# RedBoardTied.net
KiCad netlist of a schematic drawn in EAGLE
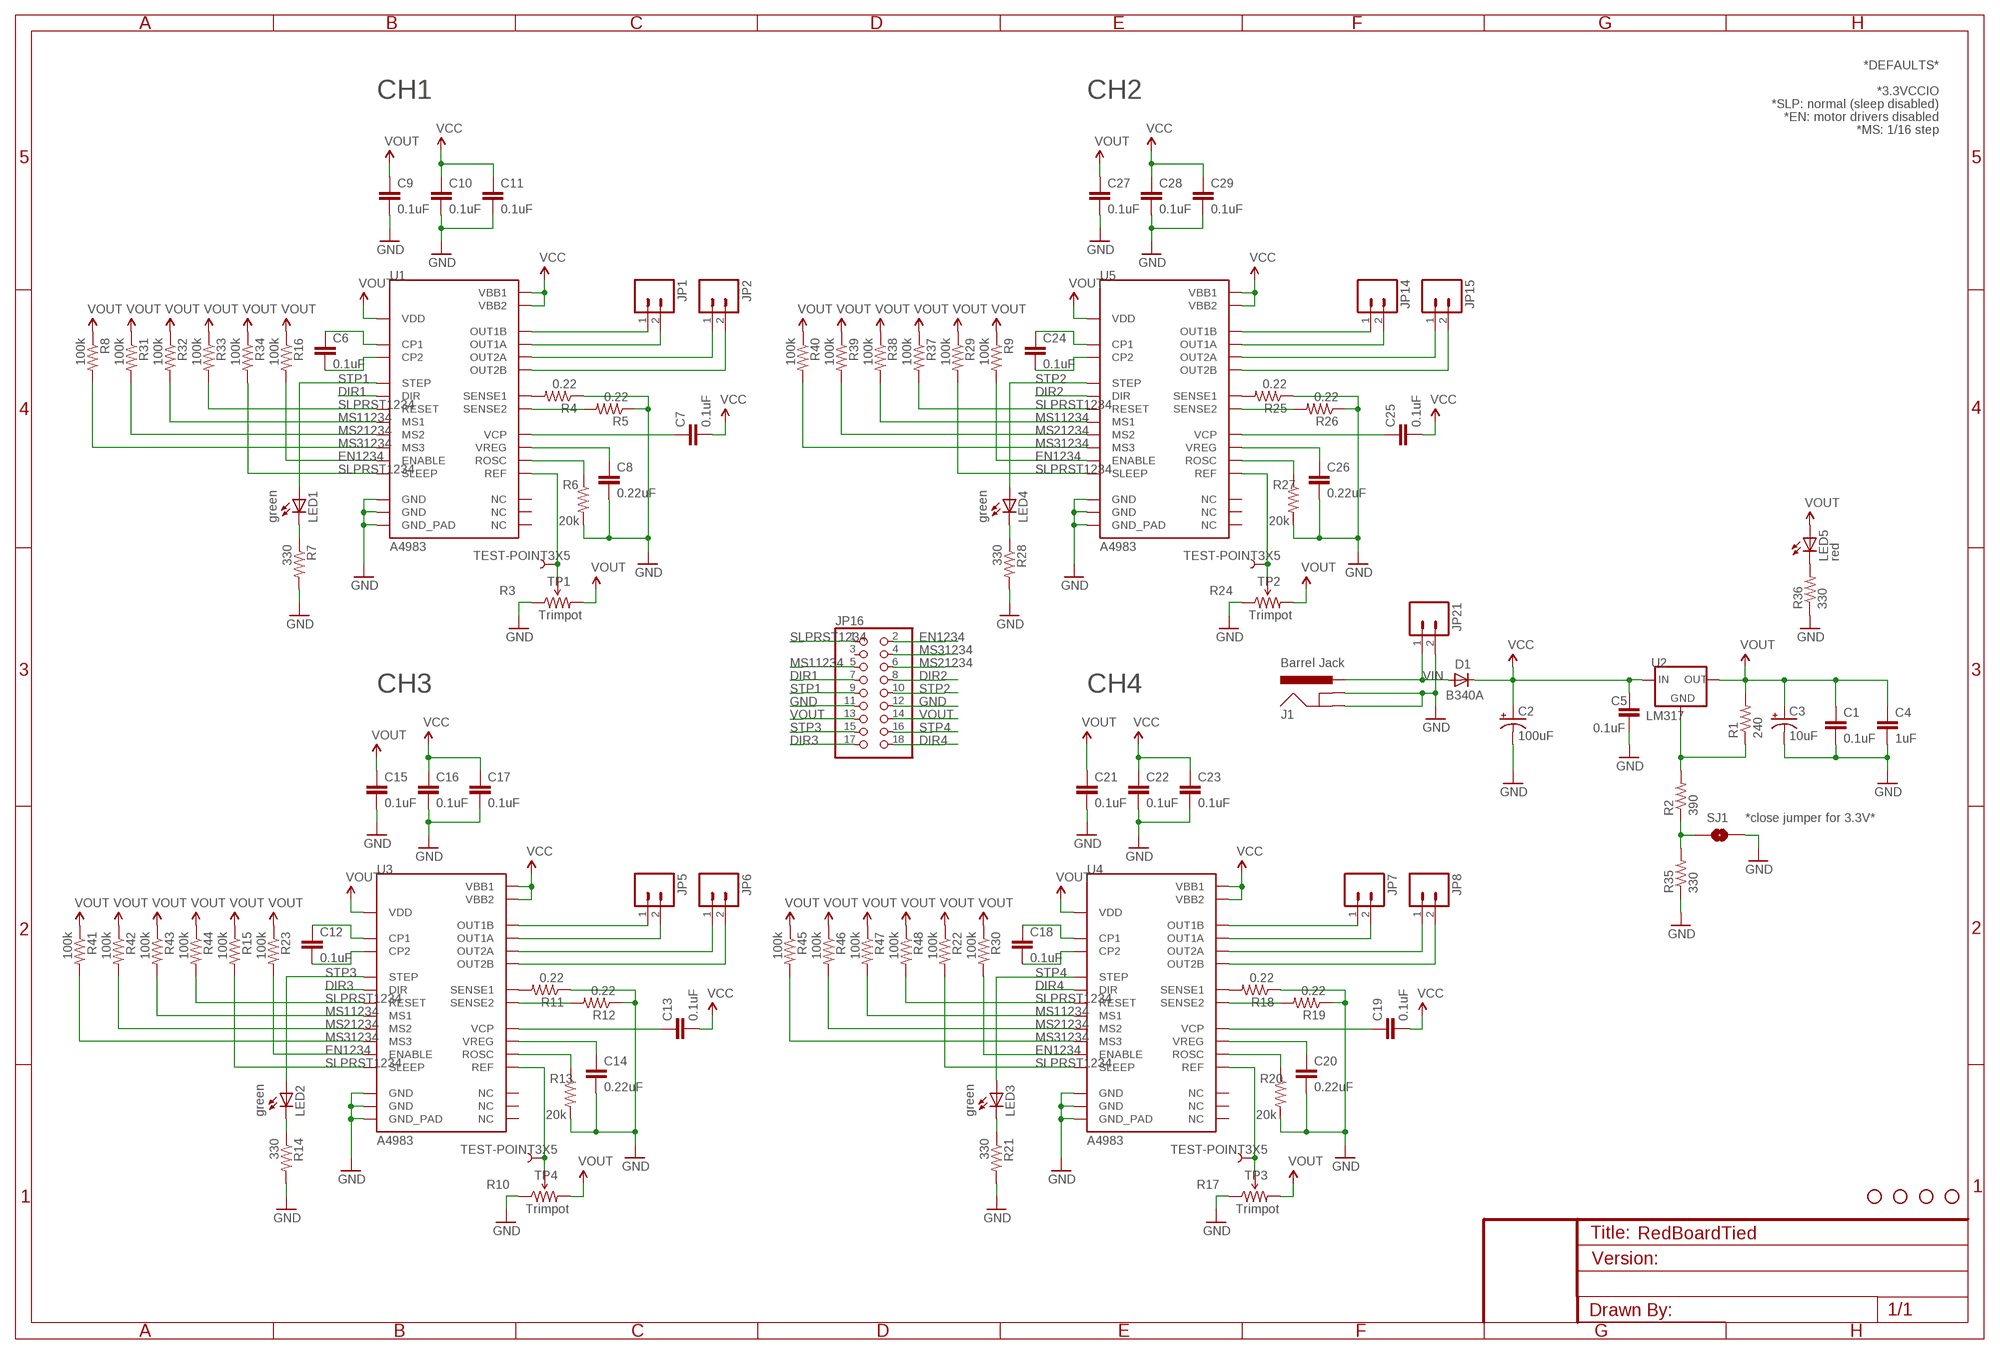
[diagram p0: schematic, sheet 1]

(export (version "E")
  (design (tool "Eeschema 10.0.6"))
  (components
    (comp (ref "C1")
      (value "0.1uF")
      (footprint "eagle-import:0402-CAP")
      (libsource (lib "eagle-import") (part "CAP0402-CAP"))
    )
    (comp (ref "C2")
      (value "100uF")
      (footprint "eagle-import:PANASONIC_G")
      (libsource (lib "eagle-import") (part "CAP_POLG"))
    )
    (comp (ref "C3")
      (value "10uF")
      (footprint "eagle-import:EIA3216")
      (libsource (lib "eagle-import") (part "CAP_POL1206"))
    )
    (comp (ref "C4")
      (value "1uF")
      (footprint "eagle-import:0805")
      (libsource (lib "eagle-import") (part "CAP0805"))
    )
    (comp (ref "C5")
      (value "0.1uF")
      (footprint "eagle-import:0402-CAP")
      (libsource (lib "eagle-import") (part "CAP0402-CAP"))
    )
    (comp (ref "C6")
      (value "0.1uF")
      (footprint "eagle-import:0402-CAP")
      (libsource (lib "eagle-import") (part "CAP0402-CAP"))
    )
    (comp (ref "C7")
      (value "0.1uF")
      (footprint "eagle-import:0402-CAP")
      (libsource (lib "eagle-import") (part "CAP0402-CAP"))
    )
    (comp (ref "C8")
      (value "0.22uF")
      (footprint "eagle-import:0402-CAP")
      (libsource (lib "eagle-import") (part "CAP0402-CAP"))
    )
    (comp (ref "C9")
      (value "0.1uF")
      (footprint "eagle-import:0402-CAP")
      (libsource (lib "eagle-import") (part "CAP0402-CAP"))
    )
    (comp (ref "C10")
      (value "0.1uF")
      (footprint "eagle-import:0402-CAP")
      (libsource (lib "eagle-import") (part "CAP0402-CAP"))
    )
    (comp (ref "C11")
      (value "0.1uF")
      (footprint "eagle-import:0402-CAP")
      (libsource (lib "eagle-import") (part "CAP0402-CAP"))
    )
    (comp (ref "C12")
      (value "0.1uF")
      (footprint "eagle-import:0402-CAP")
      (libsource (lib "eagle-import") (part "CAP0402-CAP"))
    )
    (comp (ref "C13")
      (value "0.1uF")
      (footprint "eagle-import:0402-CAP")
      (libsource (lib "eagle-import") (part "CAP0402-CAP"))
    )
    (comp (ref "C14")
      (value "0.22uF")
      (footprint "eagle-import:0402-CAP")
      (libsource (lib "eagle-import") (part "CAP0402-CAP"))
    )
    (comp (ref "C15")
      (value "0.1uF")
      (footprint "eagle-import:0402-CAP")
      (libsource (lib "eagle-import") (part "CAP0402-CAP"))
    )
    (comp (ref "C16")
      (value "0.1uF")
      (footprint "eagle-import:0402-CAP")
      (libsource (lib "eagle-import") (part "CAP0402-CAP"))
    )
    (comp (ref "C17")
      (value "0.1uF")
      (footprint "eagle-import:0402-CAP")
      (libsource (lib "eagle-import") (part "CAP0402-CAP"))
    )
    (comp (ref "C18")
      (value "0.1uF")
      (footprint "eagle-import:0402-CAP")
      (libsource (lib "eagle-import") (part "CAP0402-CAP"))
    )
    (comp (ref "C19")
      (value "0.1uF")
      (footprint "eagle-import:0402-CAP")
      (libsource (lib "eagle-import") (part "CAP0402-CAP"))
    )
    (comp (ref "C20")
      (value "0.22uF")
      (footprint "eagle-import:0402-CAP")
      (libsource (lib "eagle-import") (part "CAP0402-CAP"))
    )
    (comp (ref "C21")
      (value "0.1uF")
      (footprint "eagle-import:0402-CAP")
      (libsource (lib "eagle-import") (part "CAP0402-CAP"))
    )
    (comp (ref "C22")
      (value "0.1uF")
      (footprint "eagle-import:0402-CAP")
      (libsource (lib "eagle-import") (part "CAP0402-CAP"))
    )
    (comp (ref "C23")
      (value "0.1uF")
      (footprint "eagle-import:0402-CAP")
      (libsource (lib "eagle-import") (part "CAP0402-CAP"))
    )
    (comp (ref "C24")
      (value "0.1uF")
      (footprint "eagle-import:0402-CAP")
      (libsource (lib "eagle-import") (part "CAP0402-CAP"))
    )
    (comp (ref "C25")
      (value "0.1uF")
      (footprint "eagle-import:0402-CAP")
      (libsource (lib "eagle-import") (part "CAP0402-CAP"))
    )
    (comp (ref "C26")
      (value "0.22uF")
      (footprint "eagle-import:0402-CAP")
      (libsource (lib "eagle-import") (part "CAP0402-CAP"))
    )
    (comp (ref "C27")
      (value "0.1uF")
      (footprint "eagle-import:0402-CAP")
      (libsource (lib "eagle-import") (part "CAP0402-CAP"))
    )
    (comp (ref "C28")
      (value "0.1uF")
      (footprint "eagle-import:0402-CAP")
      (libsource (lib "eagle-import") (part "CAP0402-CAP"))
    )
    (comp (ref "C29")
      (value "0.1uF")
      (footprint "eagle-import:0402-CAP")
      (libsource (lib "eagle-import") (part "CAP0402-CAP"))
    )
    (comp (ref "D1")
      (value "B340A")
      (footprint "eagle-import:SMA-DIODE")
      (libsource (lib "eagle-import") (part "DIODESMA"))
    )
    (comp (ref "J1")
      (value "Barrel Jack")
      (footprint "eagle-import:POWER_JACK_SMD")
      (libsource (lib "eagle-import") (part "POWER_JACKSMD"))
    )
    (comp (ref "JP1")
      (value "M023.5MM_LOCK")
      (footprint "eagle-import:SCREWTERMINAL-3.5MM-2_LOCK")
      (libsource (lib "eagle-import") (part "M023.5MM_LOCK"))
    )
    (comp (ref "JP2")
      (value "M023.5MM_LOCK")
      (footprint "eagle-import:SCREWTERMINAL-3.5MM-2_LOCK")
      (libsource (lib "eagle-import") (part "M023.5MM_LOCK"))
    )
    (comp (ref "JP5")
      (value "M023.5MM_LOCK")
      (footprint "eagle-import:SCREWTERMINAL-3.5MM-2_LOCK")
      (libsource (lib "eagle-import") (part "M023.5MM_LOCK"))
    )
    (comp (ref "JP6")
      (value "M023.5MM_LOCK")
      (footprint "eagle-import:SCREWTERMINAL-3.5MM-2_LOCK")
      (libsource (lib "eagle-import") (part "M023.5MM_LOCK"))
    )
    (comp (ref "JP7")
      (value "M023.5MM_LOCK")
      (footprint "eagle-import:SCREWTERMINAL-3.5MM-2_LOCK")
      (libsource (lib "eagle-import") (part "M023.5MM_LOCK"))
    )
    (comp (ref "JP8")
      (value "M023.5MM_LOCK")
      (footprint "eagle-import:SCREWTERMINAL-3.5MM-2_LOCK")
      (libsource (lib "eagle-import") (part "M023.5MM_LOCK"))
    )
    (comp (ref "JP9")
      (value "STAND-OFF")
      (footprint "eagle-import:STAND-OFF")
      (libsource (lib "eagle-import") (part "STAND-OFF"))
    )
    (comp (ref "JP10")
      (value "STAND-OFF")
      (footprint "eagle-import:STAND-OFF")
      (libsource (lib "eagle-import") (part "STAND-OFF"))
    )
    (comp (ref "JP11")
      (value "STAND-OFF")
      (footprint "eagle-import:STAND-OFF")
      (libsource (lib "eagle-import") (part "STAND-OFF"))
    )
    (comp (ref "JP12")
      (value "STAND-OFF")
      (footprint "eagle-import:STAND-OFF")
      (libsource (lib "eagle-import") (part "STAND-OFF"))
    )
    (comp (ref "JP14")
      (value "M023.5MM_LOCK")
      (footprint "eagle-import:SCREWTERMINAL-3.5MM-2_LOCK")
      (libsource (lib "eagle-import") (part "M023.5MM_LOCK"))
    )
    (comp (ref "JP15")
      (value "M023.5MM_LOCK")
      (footprint "eagle-import:SCREWTERMINAL-3.5MM-2_LOCK")
      (libsource (lib "eagle-import") (part "M023.5MM_LOCK"))
    )
    (comp (ref "JP16")
      (value "PINHD-2X9")
      (footprint "eagle-import:2X09")
      (libsource (lib "eagle-import") (part "PINHD-2X9"))
    )
    (comp (ref "JP21")
      (value "M02PTH")
      (footprint "eagle-import:1X02")
      (libsource (lib "eagle-import") (part "M02PTH"))
    )
    (comp (ref "LED1")
      (value "green")
      (footprint "eagle-import:LED-0603")
      (libsource (lib "eagle-import") (part "LED0603"))
    )
    (comp (ref "LED2")
      (value "green")
      (footprint "eagle-import:LED-0603")
      (libsource (lib "eagle-import") (part "LED0603"))
    )
    (comp (ref "LED3")
      (value "green")
      (footprint "eagle-import:LED-0603")
      (libsource (lib "eagle-import") (part "LED0603"))
    )
    (comp (ref "LED4")
      (value "green")
      (footprint "eagle-import:LED-0603")
      (libsource (lib "eagle-import") (part "LED0603"))
    )
    (comp (ref "LED5")
      (value "red")
      (footprint "eagle-import:LED-0603")
      (libsource (lib "eagle-import") (part "LED0603"))
    )
    (comp (ref "R1")
      (value "240")
      (footprint "eagle-import:0402-RES")
      (libsource (lib "eagle-import") (part "RESISTOR0402-RES"))
    )
    (comp (ref "R2")
      (value "390")
      (footprint "eagle-import:0402-RES")
      (libsource (lib "eagle-import") (part "RESISTOR0402-RES"))
    )
    (comp (ref "R3")
      (value "Trimpot")
      (footprint "eagle-import:TRIMPOT-3MM")
      (libsource (lib "eagle-import") (part "TRIMPOTSMD"))
    )
    (comp (ref "R4")
      (value "0.22")
      (footprint "eagle-import:0805")
      (libsource (lib "eagle-import") (part "RESISTOR0805-RES"))
    )
    (comp (ref "R5")
      (value "0.22")
      (footprint "eagle-import:0805")
      (libsource (lib "eagle-import") (part "RESISTOR0805-RES"))
    )
    (comp (ref "R6")
      (value "20k")
      (footprint "eagle-import:0402-RES")
      (libsource (lib "eagle-import") (part "RESISTOR0402-RES"))
    )
    (comp (ref "R7")
      (value "330")
      (footprint "eagle-import:0402-RES")
      (libsource (lib "eagle-import") (part "RESISTOR0402-RES"))
    )
    (comp (ref "R8")
      (value "100k")
      (footprint "eagle-import:0402-RES")
      (libsource (lib "eagle-import") (part "RESISTOR0402-RES"))
    )
    (comp (ref "R9")
      (value "100k")
      (footprint "eagle-import:0402-RES")
      (libsource (lib "eagle-import") (part "RESISTOR0402-RES"))
    )
    (comp (ref "R10")
      (value "Trimpot")
      (footprint "eagle-import:TRIMPOT-3MM")
      (libsource (lib "eagle-import") (part "TRIMPOTSMD"))
    )
    (comp (ref "R11")
      (value "0.22")
      (footprint "eagle-import:0805")
      (libsource (lib "eagle-import") (part "RESISTOR0805-RES"))
    )
    (comp (ref "R12")
      (value "0.22")
      (footprint "eagle-import:0805")
      (libsource (lib "eagle-import") (part "RESISTOR0805-RES"))
    )
    (comp (ref "R13")
      (value "20k")
      (footprint "eagle-import:0402-RES")
      (libsource (lib "eagle-import") (part "RESISTOR0402-RES"))
    )
    (comp (ref "R14")
      (value "330")
      (footprint "eagle-import:0402-RES")
      (libsource (lib "eagle-import") (part "RESISTOR0402-RES"))
    )
    (comp (ref "R15")
      (value "100k")
      (footprint "eagle-import:0402-RES")
      (libsource (lib "eagle-import") (part "RESISTOR0402-RES"))
    )
    (comp (ref "R16")
      (value "100k")
      (footprint "eagle-import:0402-RES")
      (libsource (lib "eagle-import") (part "RESISTOR0402-RES"))
    )
    (comp (ref "R17")
      (value "Trimpot")
      (footprint "eagle-import:TRIMPOT-3MM")
      (libsource (lib "eagle-import") (part "TRIMPOTSMD"))
    )
    (comp (ref "R18")
      (value "0.22")
      (footprint "eagle-import:0805")
      (libsource (lib "eagle-import") (part "RESISTOR0805-RES"))
    )
    (comp (ref "R19")
      (value "0.22")
      (footprint "eagle-import:0805")
      (libsource (lib "eagle-import") (part "RESISTOR0805-RES"))
    )
    (comp (ref "R20")
      (value "20k")
      (footprint "eagle-import:0402-RES")
      (libsource (lib "eagle-import") (part "RESISTOR0402-RES"))
    )
    (comp (ref "R21")
      (value "330")
      (footprint "eagle-import:0402-RES")
      (libsource (lib "eagle-import") (part "RESISTOR0402-RES"))
    )
    (comp (ref "R22")
      (value "100k")
      (footprint "eagle-import:0402-RES")
      (libsource (lib "eagle-import") (part "RESISTOR0402-RES"))
    )
    (comp (ref "R23")
      (value "100k")
      (footprint "eagle-import:0402-RES")
      (libsource (lib "eagle-import") (part "RESISTOR0402-RES"))
    )
    (comp (ref "R24")
      (value "Trimpot")
      (footprint "eagle-import:TRIMPOT-3MM")
      (libsource (lib "eagle-import") (part "TRIMPOTSMD"))
    )
    (comp (ref "R25")
      (value "0.22")
      (footprint "eagle-import:0805")
      (libsource (lib "eagle-import") (part "RESISTOR0805-RES"))
    )
    (comp (ref "R26")
      (value "0.22")
      (footprint "eagle-import:0805")
      (libsource (lib "eagle-import") (part "RESISTOR0805-RES"))
    )
    (comp (ref "R27")
      (value "20k")
      (footprint "eagle-import:0402-RES")
      (libsource (lib "eagle-import") (part "RESISTOR0402-RES"))
    )
    (comp (ref "R28")
      (value "330")
      (footprint "eagle-import:0402-RES")
      (libsource (lib "eagle-import") (part "RESISTOR0402-RES"))
    )
    (comp (ref "R29")
      (value "100k")
      (footprint "eagle-import:0402-RES")
      (libsource (lib "eagle-import") (part "RESISTOR0402-RES"))
    )
    (comp (ref "R30")
      (value "100k")
      (footprint "eagle-import:0402-RES")
      (libsource (lib "eagle-import") (part "RESISTOR0402-RES"))
    )
    (comp (ref "R31")
      (value "100k")
      (footprint "eagle-import:0402-RES")
      (libsource (lib "eagle-import") (part "RESISTOR0402-RES"))
    )
    (comp (ref "R32")
      (value "100k")
      (footprint "eagle-import:0402-RES")
      (libsource (lib "eagle-import") (part "RESISTOR0402-RES"))
    )
    (comp (ref "R33")
      (value "100k")
      (footprint "eagle-import:0402-RES")
      (libsource (lib "eagle-import") (part "RESISTOR0402-RES"))
    )
    (comp (ref "R34")
      (value "100k")
      (footprint "eagle-import:0402-RES")
      (libsource (lib "eagle-import") (part "RESISTOR0402-RES"))
    )
    (comp (ref "R35")
      (value "330")
      (footprint "eagle-import:0402-RES")
      (libsource (lib "eagle-import") (part "RESISTOR0402-RES"))
    )
    (comp (ref "R36")
      (value "330")
      (footprint "eagle-import:0402-RES")
      (libsource (lib "eagle-import") (part "RESISTOR0402-RES"))
    )
    (comp (ref "R37")
      (value "100k")
      (footprint "eagle-import:0402-RES")
      (libsource (lib "eagle-import") (part "RESISTOR0402-RES"))
    )
    (comp (ref "R38")
      (value "100k")
      (footprint "eagle-import:0402-RES")
      (libsource (lib "eagle-import") (part "RESISTOR0402-RES"))
    )
    (comp (ref "R39")
      (value "100k")
      (footprint "eagle-import:0402-RES")
      (libsource (lib "eagle-import") (part "RESISTOR0402-RES"))
    )
    (comp (ref "R40")
      (value "100k")
      (footprint "eagle-import:0402-RES")
      (libsource (lib "eagle-import") (part "RESISTOR0402-RES"))
    )
    (comp (ref "R41")
      (value "100k")
      (footprint "eagle-import:0402-RES")
      (libsource (lib "eagle-import") (part "RESISTOR0402-RES"))
    )
    (comp (ref "R42")
      (value "100k")
      (footprint "eagle-import:0402-RES")
      (libsource (lib "eagle-import") (part "RESISTOR0402-RES"))
    )
    (comp (ref "R43")
      (value "100k")
      (footprint "eagle-import:0402-RES")
      (libsource (lib "eagle-import") (part "RESISTOR0402-RES"))
    )
    (comp (ref "R44")
      (value "100k")
      (footprint "eagle-import:0402-RES")
      (libsource (lib "eagle-import") (part "RESISTOR0402-RES"))
    )
    (comp (ref "R45")
      (value "100k")
      (footprint "eagle-import:0402-RES")
      (libsource (lib "eagle-import") (part "RESISTOR0402-RES"))
    )
    (comp (ref "R46")
      (value "100k")
      (footprint "eagle-import:0402-RES")
      (libsource (lib "eagle-import") (part "RESISTOR0402-RES"))
    )
    (comp (ref "R47")
      (value "100k")
      (footprint "eagle-import:0402-RES")
      (libsource (lib "eagle-import") (part "RESISTOR0402-RES"))
    )
    (comp (ref "R48")
      (value "100k")
      (footprint "eagle-import:0402-RES")
      (libsource (lib "eagle-import") (part "RESISTOR0402-RES"))
    )
    (comp (ref "SJ1")
      (value "SOLDERJUMPERNO")
      (footprint "eagle-import:SJ_2S-NO")
      (libsource (lib "eagle-import") (part "SOLDERJUMPERNO"))
    )
    (comp (ref "TP1")
      (value "TEST-POINT3X5")
      (footprint "eagle-import:PAD.03X.05")
      (libsource (lib "eagle-import") (part "TEST-POINT3X5"))
    )
    (comp (ref "TP2")
      (value "TEST-POINT3X5")
      (footprint "eagle-import:PAD.03X.05")
      (libsource (lib "eagle-import") (part "TEST-POINT3X5"))
    )
    (comp (ref "TP3")
      (value "TEST-POINT3X5")
      (footprint "eagle-import:PAD.03X.05")
      (libsource (lib "eagle-import") (part "TEST-POINT3X5"))
    )
    (comp (ref "TP4")
      (value "TEST-POINT3X5")
      (footprint "eagle-import:PAD.03X.05")
      (libsource (lib "eagle-import") (part "TEST-POINT3X5"))
    )
    (comp (ref "U1")
      (value "A4983")
      (footprint "eagle-import:QFN-28-5MM")
      (libsource (lib "eagle-import") (part "A4983"))
    )
    (comp (ref "U2")
      (value "LM317")
      (footprint "eagle-import:DPAK")
      (libsource (lib "eagle-import") (part "V_REG_MC33269DT"))
    )
    (comp (ref "U3")
      (value "A4983")
      (footprint "eagle-import:QFN-28-5MM")
      (libsource (lib "eagle-import") (part "A4983"))
    )
    (comp (ref "U4")
      (value "A4983")
      (footprint "eagle-import:QFN-28-5MM")
      (libsource (lib "eagle-import") (part "A4983"))
    )
    (comp (ref "U5")
      (value "A4983")
      (footprint "eagle-import:QFN-28-5MM")
      (libsource (lib "eagle-import") (part "A4983"))
    )
  )
  (nets
    (net (code "1") (name "/DIR1") (class "Default")
      (node (ref "JP16") (pin "7") (pinfunction "7_7") (pintype "passive"))
      (node (ref "U1") (pin "P$19") (pinfunction "DIR_P$19") (pintype "input"))
    )
    (net (code "2") (name "/DIR2") (class "Default")
      (node (ref "JP16") (pin "8") (pinfunction "8_8") (pintype "passive"))
      (node (ref "U5") (pin "P$19") (pinfunction "DIR_P$19") (pintype "input"))
    )
    (net (code "3") (name "/DIR3") (class "Default")
      (node (ref "JP16") (pin "17") (pinfunction "17_17") (pintype "passive"))
      (node (ref "U3") (pin "P$19") (pinfunction "DIR_P$19") (pintype "input"))
    )
    (net (code "4") (name "/DIR4") (class "Default")
      (node (ref "JP16") (pin "18") (pinfunction "18_18") (pintype "passive"))
      (node (ref "U4") (pin "P$19") (pinfunction "DIR_P$19") (pintype "input"))
    )
    (net (code "5") (name "/EN1234") (class "Default")
      (node (ref "JP16") (pin "2") (pinfunction "2_2") (pintype "passive"))
      (node (ref "R16") (pin "2") (pinfunction "2_2") (pintype "passive"))
      (node (ref "R23") (pin "2") (pinfunction "2_2") (pintype "passive"))
      (node (ref "R30") (pin "2") (pinfunction "2_2") (pintype "passive"))
      (node (ref "R9") (pin "2") (pinfunction "2_2") (pintype "passive"))
      (node (ref "U1") (pin "P$2") (pinfunction "ENABLE_P$2") (pintype "input"))
      (node (ref "U3") (pin "P$2") (pinfunction "ENABLE_P$2") (pintype "input"))
      (node (ref "U4") (pin "P$2") (pinfunction "ENABLE_P$2") (pintype "input"))
      (node (ref "U5") (pin "P$2") (pinfunction "ENABLE_P$2") (pintype "input"))
    )
    (net (code "6") (name "/MS11234") (class "Default")
      (node (ref "JP16") (pin "5") (pinfunction "5_5") (pintype "passive"))
      (node (ref "R32") (pin "2") (pinfunction "2_2") (pintype "passive"))
      (node (ref "R38") (pin "2") (pinfunction "2_2") (pintype "passive"))
      (node (ref "R43") (pin "2") (pinfunction "2_2") (pintype "passive"))
      (node (ref "R47") (pin "2") (pinfunction "2_2") (pintype "passive"))
      (node (ref "U1") (pin "P$9") (pinfunction "MS1_P$9") (pintype "input"))
      (node (ref "U3") (pin "P$9") (pinfunction "MS1_P$9") (pintype "input"))
      (node (ref "U4") (pin "P$9") (pinfunction "MS1_P$9") (pintype "input"))
      (node (ref "U5") (pin "P$9") (pinfunction "MS1_P$9") (pintype "input"))
    )
    (net (code "7") (name "/MS21234") (class "Default")
      (node (ref "JP16") (pin "6") (pinfunction "6_6") (pintype "passive"))
      (node (ref "R31") (pin "2") (pinfunction "2_2") (pintype "passive"))
      (node (ref "R39") (pin "2") (pinfunction "2_2") (pintype "passive"))
      (node (ref "R42") (pin "2") (pinfunction "2_2") (pintype "passive"))
      (node (ref "R46") (pin "2") (pinfunction "2_2") (pintype "passive"))
      (node (ref "U1") (pin "P$10") (pinfunction "MS2_P$10") (pintype "input"))
      (node (ref "U3") (pin "P$10") (pinfunction "MS2_P$10") (pintype "input"))
      (node (ref "U4") (pin "P$10") (pinfunction "MS2_P$10") (pintype "input"))
      (node (ref "U5") (pin "P$10") (pinfunction "MS2_P$10") (pintype "input"))
    )
    (net (code "8") (name "/MS31234") (class "Default")
      (node (ref "JP16") (pin "4") (pinfunction "4_4") (pintype "passive"))
      (node (ref "R40") (pin "2") (pinfunction "2_2") (pintype "passive"))
      (node (ref "R41") (pin "2") (pinfunction "2_2") (pintype "passive"))
      (node (ref "R45") (pin "2") (pinfunction "2_2") (pintype "passive"))
      (node (ref "R8") (pin "2") (pinfunction "2_2") (pintype "passive"))
      (node (ref "U1") (pin "P$11") (pinfunction "MS3_P$11") (pintype "input"))
      (node (ref "U3") (pin "P$11") (pinfunction "MS3_P$11") (pintype "input"))
      (node (ref "U4") (pin "P$11") (pinfunction "MS3_P$11") (pintype "input"))
      (node (ref "U5") (pin "P$11") (pinfunction "MS3_P$11") (pintype "input"))
    )
    (net (code "9") (name "/SLPRST1234") (class "Default")
      (node (ref "JP16") (pin "1") (pinfunction "1_1") (pintype "passive"))
      (node (ref "R15") (pin "2") (pinfunction "2_2") (pintype "passive"))
      (node (ref "R22") (pin "2") (pinfunction "2_2") (pintype "passive"))
      (node (ref "R29") (pin "2") (pinfunction "2_2") (pintype "passive"))
      (node (ref "R33") (pin "2") (pinfunction "2_2") (pintype "passive"))
      (node (ref "R34") (pin "2") (pinfunction "2_2") (pintype "passive"))
      (node (ref "R37") (pin "2") (pinfunction "2_2") (pintype "passive"))
      (node (ref "R44") (pin "2") (pinfunction "2_2") (pintype "passive"))
      (node (ref "R48") (pin "2") (pinfunction "2_2") (pintype "passive"))
      (node (ref "U1") (pin "P$12") (pinfunction "RESET_P$12") (pintype "input"))
      (node (ref "U1") (pin "P$14") (pinfunction "SLEEP_P$14") (pintype "input"))
      (node (ref "U3") (pin "P$12") (pinfunction "RESET_P$12") (pintype "input"))
      (node (ref "U3") (pin "P$14") (pinfunction "SLEEP_P$14") (pintype "input"))
      (node (ref "U4") (pin "P$12") (pinfunction "RESET_P$12") (pintype "input"))
      (node (ref "U4") (pin "P$14") (pinfunction "SLEEP_P$14") (pintype "input"))
      (node (ref "U5") (pin "P$12") (pinfunction "RESET_P$12") (pintype "input"))
      (node (ref "U5") (pin "P$14") (pinfunction "SLEEP_P$14") (pintype "input"))
    )
    (net (code "10") (name "/STP1") (class "Default")
      (node (ref "JP16") (pin "9") (pinfunction "9_9") (pintype "passive"))
      (node (ref "LED1") (pin "A") (pinfunction "A_A") (pintype "passive"))
      (node (ref "U1") (pin "P$16") (pinfunction "STEP_P$16") (pintype "input"))
    )
    (net (code "11") (name "/STP2") (class "Default")
      (node (ref "JP16") (pin "10") (pinfunction "10_10") (pintype "passive"))
      (node (ref "LED4") (pin "A") (pinfunction "A_A") (pintype "passive"))
      (node (ref "U5") (pin "P$16") (pinfunction "STEP_P$16") (pintype "input"))
    )
    (net (code "12") (name "/STP3") (class "Default")
      (node (ref "JP16") (pin "15") (pinfunction "15_15") (pintype "passive"))
      (node (ref "LED2") (pin "A") (pinfunction "A_A") (pintype "passive"))
      (node (ref "U3") (pin "P$16") (pinfunction "STEP_P$16") (pintype "input"))
    )
    (net (code "13") (name "/STP4") (class "Default")
      (node (ref "JP16") (pin "16") (pinfunction "16_16") (pintype "passive"))
      (node (ref "LED3") (pin "A") (pinfunction "A_A") (pintype "passive"))
      (node (ref "U4") (pin "P$16") (pinfunction "STEP_P$16") (pintype "input"))
    )
    (net (code "14") (name "/VIN") (class "Default")
      (node (ref "D1") (pin "A") (pinfunction "A_A") (pintype "passive"))
      (node (ref "J1") (pin "VIN0") (pinfunction "PWR_VIN0") (pintype "bidirectional"))
      (node (ref "JP21") (pin "1") (pinfunction "1_1") (pintype "passive"))
    )
    (net (code "15") (name "GND") (class "Default")
      (node (ref "C1") (pin "2") (pinfunction "2_2") (pintype "passive"))
      (node (ref "C10") (pin "2") (pinfunction "2_2") (pintype "passive"))
      (node (ref "C11") (pin "2") (pinfunction "2_2") (pintype "passive"))
      (node (ref "C14") (pin "2") (pinfunction "2_2") (pintype "passive"))
      (node (ref "C15") (pin "2") (pinfunction "2_2") (pintype "passive"))
      (node (ref "C16") (pin "2") (pinfunction "2_2") (pintype "passive"))
      (node (ref "C17") (pin "2") (pinfunction "2_2") (pintype "passive"))
      (node (ref "C2") (pin "-") (pinfunction "-_-") (pintype "passive"))
      (node (ref "C20") (pin "2") (pinfunction "2_2") (pintype "passive"))
      (node (ref "C21") (pin "2") (pinfunction "2_2") (pintype "passive"))
      (node (ref "C22") (pin "2") (pinfunction "2_2") (pintype "passive"))
      (node (ref "C23") (pin "2") (pinfunction "2_2") (pintype "passive"))
      (node (ref "C26") (pin "2") (pinfunction "2_2") (pintype "passive"))
      (node (ref "C27") (pin "2") (pinfunction "2_2") (pintype "passive"))
      (node (ref "C28") (pin "2") (pinfunction "2_2") (pintype "passive"))
      (node (ref "C29") (pin "2") (pinfunction "2_2") (pintype "passive"))
      (node (ref "C3") (pin "C") (pinfunction "-_C") (pintype "passive"))
      (node (ref "C4") (pin "2") (pinfunction "2_2") (pintype "passive"))
      (node (ref "C5") (pin "2") (pinfunction "2_2") (pintype "passive"))
      (node (ref "C8") (pin "2") (pinfunction "2_2") (pintype "passive"))
      (node (ref "C9") (pin "2") (pinfunction "2_2") (pintype "passive"))
      (node (ref "J1") (pin "GND") (pinfunction "GNDBREAK_GND") (pintype "bidirectional"))
      (node (ref "J1") (pin "P$4") (pinfunction "GND_P$4") (pintype "bidirectional"))
      (node (ref "JP16") (pin "11") (pinfunction "11_11") (pintype "passive"))
      (node (ref "JP16") (pin "12") (pinfunction "12_12") (pintype "passive"))
      (node (ref "JP21") (pin "2") (pinfunction "2_2") (pintype "passive"))
      (node (ref "R10") (pin "1") (pinfunction "CCW_1") (pintype "passive"))
      (node (ref "R11") (pin "1") (pinfunction "1_1") (pintype "passive"))
      (node (ref "R12") (pin "1") (pinfunction "1_1") (pintype "passive"))
      (node (ref "R13") (pin "2") (pinfunction "2_2") (pintype "passive"))
      (node (ref "R14") (pin "2") (pinfunction "2_2") (pintype "passive"))
      (node (ref "R17") (pin "1") (pinfunction "CCW_1") (pintype "passive"))
      (node (ref "R18") (pin "1") (pinfunction "1_1") (pintype "passive"))
      (node (ref "R19") (pin "1") (pinfunction "1_1") (pintype "passive"))
      (node (ref "R20") (pin "2") (pinfunction "2_2") (pintype "passive"))
      (node (ref "R21") (pin "2") (pinfunction "2_2") (pintype "passive"))
      (node (ref "R24") (pin "1") (pinfunction "CCW_1") (pintype "passive"))
      (node (ref "R25") (pin "1") (pinfunction "1_1") (pintype "passive"))
      (node (ref "R26") (pin "1") (pinfunction "1_1") (pintype "passive"))
      (node (ref "R27") (pin "2") (pinfunction "2_2") (pintype "passive"))
      (node (ref "R28") (pin "2") (pinfunction "2_2") (pintype "passive"))
      (node (ref "R3") (pin "1") (pinfunction "CCW_1") (pintype "passive"))
      (node (ref "R35") (pin "1") (pinfunction "1_1") (pintype "passive"))
      (node (ref "R36") (pin "1") (pinfunction "1_1") (pintype "passive"))
      (node (ref "R4") (pin "1") (pinfunction "1_1") (pintype "passive"))
      (node (ref "R5") (pin "1") (pinfunction "1_1") (pintype "passive"))
      (node (ref "R6") (pin "2") (pinfunction "2_2") (pintype "passive"))
      (node (ref "R7") (pin "2") (pinfunction "2_2") (pintype "passive"))
      (node (ref "SJ1") (pin "2") (pinfunction "2_2") (pintype "passive"))
      (node (ref "U1") (pin "P$18") (pinfunction "GND_P$18") (pintype "power_in"))
      (node (ref "U1") (pin "P$29") (pinfunction "GND_PAD_P$29") (pintype "power_in"))
      (node (ref "U1") (pin "P$3") (pinfunction "GND_P$3") (pintype "power_in"))
      (node (ref "U3") (pin "P$18") (pinfunction "GND_P$18") (pintype "power_in"))
      (node (ref "U3") (pin "P$29") (pinfunction "GND_PAD_P$29") (pintype "power_in"))
      (node (ref "U3") (pin "P$3") (pinfunction "GND_P$3") (pintype "power_in"))
      (node (ref "U4") (pin "P$18") (pinfunction "GND_P$18") (pintype "power_in"))
      (node (ref "U4") (pin "P$29") (pinfunction "GND_PAD_P$29") (pintype "power_in"))
      (node (ref "U4") (pin "P$3") (pinfunction "GND_P$3") (pintype "power_in"))
      (node (ref "U5") (pin "P$18") (pinfunction "GND_P$18") (pintype "power_in"))
      (node (ref "U5") (pin "P$29") (pinfunction "GND_PAD_P$29") (pintype "power_in"))
      (node (ref "U5") (pin "P$3") (pinfunction "GND_P$3") (pintype "power_in"))
    )
    (net (code "16") (name "Net-(LED1-PadC)") (class "Default")
      (node (ref "LED1") (pin "C") (pinfunction "C_C") (pintype "passive"))
      (node (ref "R7") (pin "1") (pinfunction "1_1") (pintype "passive"))
    )
    (net (code "17") (name "Net-(LED2-PadC)") (class "Default")
      (node (ref "LED2") (pin "C") (pinfunction "C_C") (pintype "passive"))
      (node (ref "R14") (pin "1") (pinfunction "1_1") (pintype "passive"))
    )
    (net (code "18") (name "Net-(LED3-PadC)") (class "Default")
      (node (ref "LED3") (pin "C") (pinfunction "C_C") (pintype "passive"))
      (node (ref "R21") (pin "1") (pinfunction "1_1") (pintype "passive"))
    )
    (net (code "19") (name "Net-(LED4-PadC)") (class "Default")
      (node (ref "LED4") (pin "C") (pinfunction "C_C") (pintype "passive"))
      (node (ref "R28") (pin "1") (pinfunction "1_1") (pintype "passive"))
    )
    (net (code "20") (name "Net-(LED5-PadC)") (class "Default")
      (node (ref "LED5") (pin "C") (pinfunction "C_C") (pintype "passive"))
      (node (ref "R36") (pin "2") (pinfunction "2_2") (pintype "passive"))
    )
    (net (code "21") (name "Net-(R2-Pad1)") (class "Default")
      (node (ref "R2") (pin "1") (pinfunction "1_1") (pintype "passive"))
      (node (ref "R35") (pin "2") (pinfunction "2_2") (pintype "passive"))
      (node (ref "SJ1") (pin "1") (pinfunction "1_1") (pintype "passive"))
    )
    (net (code "22") (name "Net-(R3-WIPER)") (class "Default")
      (node (ref "R3") (pin "2") (pinfunction "WIPER_2") (pintype "passive"))
      (node (ref "TP1") (pin "P$1") (pinfunction "1_P$1") (pintype "bidirectional"))
      (node (ref "U1") (pin "P$17") (pinfunction "REF_P$17") (pintype "bidirectional"))
    )
    (net (code "23") (name "Net-(R10-WIPER)") (class "Default")
      (node (ref "R10") (pin "2") (pinfunction "WIPER_2") (pintype "passive"))
      (node (ref "TP4") (pin "P$1") (pinfunction "1_P$1") (pintype "bidirectional"))
      (node (ref "U3") (pin "P$17") (pinfunction "REF_P$17") (pintype "bidirectional"))
    )
    (net (code "24") (name "Net-(R17-WIPER)") (class "Default")
      (node (ref "R17") (pin "2") (pinfunction "WIPER_2") (pintype "passive"))
      (node (ref "TP3") (pin "P$1") (pinfunction "1_P$1") (pintype "bidirectional"))
      (node (ref "U4") (pin "P$17") (pinfunction "REF_P$17") (pintype "bidirectional"))
    )
    (net (code "25") (name "Net-(R24-WIPER)") (class "Default")
      (node (ref "R24") (pin "2") (pinfunction "WIPER_2") (pintype "passive"))
      (node (ref "TP2") (pin "P$1") (pinfunction "1_P$1") (pintype "bidirectional"))
      (node (ref "U5") (pin "P$17") (pinfunction "REF_P$17") (pintype "bidirectional"))
    )
    (net (code "26") (name "Net-(U1-CP1)") (class "Default")
      (node (ref "C6") (pin "1") (pinfunction "1_1") (pintype "passive"))
      (node (ref "U1") (pin "P$4") (pinfunction "CP1_P$4") (pintype "bidirectional"))
    )
    (net (code "27") (name "Net-(U1-CP2)") (class "Default")
      (node (ref "C6") (pin "2") (pinfunction "2_2") (pintype "passive"))
      (node (ref "U1") (pin "P$5") (pinfunction "CP2_P$5") (pintype "bidirectional"))
    )
    (net (code "28") (name "Net-(U1-OUT1A)") (class "Default")
      (node (ref "JP1") (pin "2") (pinfunction "2_2") (pintype "passive"))
      (node (ref "U1") (pin "P$24") (pinfunction "OUT1A_P$24") (pintype "bidirectional"))
    )
    (net (code "29") (name "Net-(U1-OUT1B)") (class "Default")
      (node (ref "JP1") (pin "1") (pinfunction "1_1") (pintype "passive"))
      (node (ref "U1") (pin "P$21") (pinfunction "OUT1B_P$21") (pintype "bidirectional"))
    )
    (net (code "30") (name "Net-(U1-OUT2A)") (class "Default")
      (node (ref "JP2") (pin "1") (pinfunction "1_1") (pintype "passive"))
      (node (ref "U1") (pin "P$26") (pinfunction "OUT2A_P$26") (pintype "bidirectional"))
    )
    (net (code "31") (name "Net-(U1-OUT2B)") (class "Default")
      (node (ref "JP2") (pin "2") (pinfunction "2_2") (pintype "passive"))
      (node (ref "U1") (pin "P$1") (pinfunction "OUT2B_P$1") (pintype "bidirectional"))
    )
    (net (code "32") (name "Net-(U1-ROSC)") (class "Default")
      (node (ref "R6") (pin "1") (pinfunction "1_1") (pintype "passive"))
      (node (ref "U1") (pin "P$13") (pinfunction "ROSC_P$13") (pintype "bidirectional"))
    )
    (net (code "33") (name "Net-(U1-SENSE1)") (class "Default")
      (node (ref "R4") (pin "2") (pinfunction "2_2") (pintype "passive"))
      (node (ref "U1") (pin "P$23") (pinfunction "SENSE1_P$23") (pintype "bidirectional"))
    )
    (net (code "34") (name "Net-(U1-SENSE2)") (class "Default")
      (node (ref "R5") (pin "2") (pinfunction "2_2") (pintype "passive"))
      (node (ref "U1") (pin "P$27") (pinfunction "SENSE2_P$27") (pintype "bidirectional"))
    )
    (net (code "35") (name "Net-(U1-VCP)") (class "Default")
      (node (ref "C7") (pin "1") (pinfunction "1_1") (pintype "passive"))
      (node (ref "U1") (pin "P$6") (pinfunction "VCP_P$6") (pintype "bidirectional"))
    )
    (net (code "36") (name "Net-(U1-VREG)") (class "Default")
      (node (ref "C8") (pin "1") (pinfunction "1_1") (pintype "passive"))
      (node (ref "U1") (pin "P$8") (pinfunction "VREG_P$8") (pintype "bidirectional"))
    )
    (net (code "37") (name "Net-(U2-GND)") (class "Default")
      (node (ref "R1") (pin "1") (pinfunction "1_1") (pintype "passive"))
      (node (ref "R2") (pin "2") (pinfunction "2_2") (pintype "passive"))
      (node (ref "U2") (pin "1") (pinfunction "GND_1") (pintype "input"))
    )
    (net (code "38") (name "Net-(U3-CP1)") (class "Default")
      (node (ref "C12") (pin "1") (pinfunction "1_1") (pintype "passive"))
      (node (ref "U3") (pin "P$4") (pinfunction "CP1_P$4") (pintype "bidirectional"))
    )
    (net (code "39") (name "Net-(U3-CP2)") (class "Default")
      (node (ref "C12") (pin "2") (pinfunction "2_2") (pintype "passive"))
      (node (ref "U3") (pin "P$5") (pinfunction "CP2_P$5") (pintype "bidirectional"))
    )
    (net (code "40") (name "Net-(U3-OUT1A)") (class "Default")
      (node (ref "JP5") (pin "2") (pinfunction "2_2") (pintype "passive"))
      (node (ref "U3") (pin "P$24") (pinfunction "OUT1A_P$24") (pintype "bidirectional"))
    )
    (net (code "41") (name "Net-(U3-OUT1B)") (class "Default")
      (node (ref "JP5") (pin "1") (pinfunction "1_1") (pintype "passive"))
      (node (ref "U3") (pin "P$21") (pinfunction "OUT1B_P$21") (pintype "bidirectional"))
    )
    (net (code "42") (name "Net-(U3-OUT2A)") (class "Default")
      (node (ref "JP6") (pin "1") (pinfunction "1_1") (pintype "passive"))
      (node (ref "U3") (pin "P$26") (pinfunction "OUT2A_P$26") (pintype "bidirectional"))
    )
    (net (code "43") (name "Net-(U3-OUT2B)") (class "Default")
      (node (ref "JP6") (pin "2") (pinfunction "2_2") (pintype "passive"))
      (node (ref "U3") (pin "P$1") (pinfunction "OUT2B_P$1") (pintype "bidirectional"))
    )
    (net (code "44") (name "Net-(U3-ROSC)") (class "Default")
      (node (ref "R13") (pin "1") (pinfunction "1_1") (pintype "passive"))
      (node (ref "U3") (pin "P$13") (pinfunction "ROSC_P$13") (pintype "bidirectional"))
    )
    (net (code "45") (name "Net-(U3-SENSE1)") (class "Default")
      (node (ref "R11") (pin "2") (pinfunction "2_2") (pintype "passive"))
      (node (ref "U3") (pin "P$23") (pinfunction "SENSE1_P$23") (pintype "bidirectional"))
    )
    (net (code "46") (name "Net-(U3-SENSE2)") (class "Default")
      (node (ref "R12") (pin "2") (pinfunction "2_2") (pintype "passive"))
      (node (ref "U3") (pin "P$27") (pinfunction "SENSE2_P$27") (pintype "bidirectional"))
    )
    (net (code "47") (name "Net-(U3-VCP)") (class "Default")
      (node (ref "C13") (pin "1") (pinfunction "1_1") (pintype "passive"))
      (node (ref "U3") (pin "P$6") (pinfunction "VCP_P$6") (pintype "bidirectional"))
    )
    (net (code "48") (name "Net-(U3-VREG)") (class "Default")
      (node (ref "C14") (pin "1") (pinfunction "1_1") (pintype "passive"))
      (node (ref "U3") (pin "P$8") (pinfunction "VREG_P$8") (pintype "bidirectional"))
    )
    (net (code "49") (name "Net-(U4-CP1)") (class "Default")
      (node (ref "C18") (pin "1") (pinfunction "1_1") (pintype "passive"))
      (node (ref "U4") (pin "P$4") (pinfunction "CP1_P$4") (pintype "bidirectional"))
    )
    (net (code "50") (name "Net-(U4-CP2)") (class "Default")
      (node (ref "C18") (pin "2") (pinfunction "2_2") (pintype "passive"))
      (node (ref "U4") (pin "P$5") (pinfunction "CP2_P$5") (pintype "bidirectional"))
    )
    (net (code "51") (name "Net-(U4-OUT1A)") (class "Default")
      (node (ref "JP7") (pin "2") (pinfunction "2_2") (pintype "passive"))
      (node (ref "U4") (pin "P$24") (pinfunction "OUT1A_P$24") (pintype "bidirectional"))
    )
    (net (code "52") (name "Net-(U4-OUT1B)") (class "Default")
      (node (ref "JP7") (pin "1") (pinfunction "1_1") (pintype "passive"))
      (node (ref "U4") (pin "P$21") (pinfunction "OUT1B_P$21") (pintype "bidirectional"))
    )
    (net (code "53") (name "Net-(U4-OUT2A)") (class "Default")
      (node (ref "JP8") (pin "1") (pinfunction "1_1") (pintype "passive"))
      (node (ref "U4") (pin "P$26") (pinfunction "OUT2A_P$26") (pintype "bidirectional"))
    )
    (net (code "54") (name "Net-(U4-OUT2B)") (class "Default")
      (node (ref "JP8") (pin "2") (pinfunction "2_2") (pintype "passive"))
      (node (ref "U4") (pin "P$1") (pinfunction "OUT2B_P$1") (pintype "bidirectional"))
    )
    (net (code "55") (name "Net-(U4-ROSC)") (class "Default")
      (node (ref "R20") (pin "1") (pinfunction "1_1") (pintype "passive"))
      (node (ref "U4") (pin "P$13") (pinfunction "ROSC_P$13") (pintype "bidirectional"))
    )
    (net (code "56") (name "Net-(U4-SENSE1)") (class "Default")
      (node (ref "R18") (pin "2") (pinfunction "2_2") (pintype "passive"))
      (node (ref "U4") (pin "P$23") (pinfunction "SENSE1_P$23") (pintype "bidirectional"))
    )
    (net (code "57") (name "Net-(U4-SENSE2)") (class "Default")
      (node (ref "R19") (pin "2") (pinfunction "2_2") (pintype "passive"))
      (node (ref "U4") (pin "P$27") (pinfunction "SENSE2_P$27") (pintype "bidirectional"))
    )
    (net (code "58") (name "Net-(U4-VCP)") (class "Default")
      (node (ref "C19") (pin "1") (pinfunction "1_1") (pintype "passive"))
      (node (ref "U4") (pin "P$6") (pinfunction "VCP_P$6") (pintype "bidirectional"))
    )
    (net (code "59") (name "Net-(U4-VREG)") (class "Default")
      (node (ref "C20") (pin "1") (pinfunction "1_1") (pintype "passive"))
      (node (ref "U4") (pin "P$8") (pinfunction "VREG_P$8") (pintype "bidirectional"))
    )
    (net (code "60") (name "Net-(U5-CP1)") (class "Default")
      (node (ref "C24") (pin "1") (pinfunction "1_1") (pintype "passive"))
      (node (ref "U5") (pin "P$4") (pinfunction "CP1_P$4") (pintype "bidirectional"))
    )
    (net (code "61") (name "Net-(U5-CP2)") (class "Default")
      (node (ref "C24") (pin "2") (pinfunction "2_2") (pintype "passive"))
      (node (ref "U5") (pin "P$5") (pinfunction "CP2_P$5") (pintype "bidirectional"))
    )
    (net (code "62") (name "Net-(U5-OUT1A)") (class "Default")
      (node (ref "JP14") (pin "2") (pinfunction "2_2") (pintype "passive"))
      (node (ref "U5") (pin "P$24") (pinfunction "OUT1A_P$24") (pintype "bidirectional"))
    )
    (net (code "63") (name "Net-(U5-OUT1B)") (class "Default")
      (node (ref "JP14") (pin "1") (pinfunction "1_1") (pintype "passive"))
      (node (ref "U5") (pin "P$21") (pinfunction "OUT1B_P$21") (pintype "bidirectional"))
    )
    (net (code "64") (name "Net-(U5-OUT2A)") (class "Default")
      (node (ref "JP15") (pin "1") (pinfunction "1_1") (pintype "passive"))
      (node (ref "U5") (pin "P$26") (pinfunction "OUT2A_P$26") (pintype "bidirectional"))
    )
    (net (code "65") (name "Net-(U5-OUT2B)") (class "Default")
      (node (ref "JP15") (pin "2") (pinfunction "2_2") (pintype "passive"))
      (node (ref "U5") (pin "P$1") (pinfunction "OUT2B_P$1") (pintype "bidirectional"))
    )
    (net (code "66") (name "Net-(U5-ROSC)") (class "Default")
      (node (ref "R27") (pin "1") (pinfunction "1_1") (pintype "passive"))
      (node (ref "U5") (pin "P$13") (pinfunction "ROSC_P$13") (pintype "bidirectional"))
    )
    (net (code "67") (name "Net-(U5-SENSE1)") (class "Default")
      (node (ref "R25") (pin "2") (pinfunction "2_2") (pintype "passive"))
      (node (ref "U5") (pin "P$23") (pinfunction "SENSE1_P$23") (pintype "bidirectional"))
    )
    (net (code "68") (name "Net-(U5-SENSE2)") (class "Default")
      (node (ref "R26") (pin "2") (pinfunction "2_2") (pintype "passive"))
      (node (ref "U5") (pin "P$27") (pinfunction "SENSE2_P$27") (pintype "bidirectional"))
    )
    (net (code "69") (name "Net-(U5-VCP)") (class "Default")
      (node (ref "C25") (pin "1") (pinfunction "1_1") (pintype "passive"))
      (node (ref "U5") (pin "P$6") (pinfunction "VCP_P$6") (pintype "bidirectional"))
    )
    (net (code "70") (name "Net-(U5-VREG)") (class "Default")
      (node (ref "C26") (pin "1") (pinfunction "1_1") (pintype "passive"))
      (node (ref "U5") (pin "P$8") (pinfunction "VREG_P$8") (pintype "bidirectional"))
    )
    (net (code "71") (name "VCC") (class "Default")
      (node (ref "C10") (pin "1") (pinfunction "1_1") (pintype "passive"))
      (node (ref "C11") (pin "1") (pinfunction "1_1") (pintype "passive"))
      (node (ref "C13") (pin "2") (pinfunction "2_2") (pintype "passive"))
      (node (ref "C16") (pin "1") (pinfunction "1_1") (pintype "passive"))
      (node (ref "C17") (pin "1") (pinfunction "1_1") (pintype "passive"))
      (node (ref "C19") (pin "2") (pinfunction "2_2") (pintype "passive"))
      (node (ref "C2") (pin "+") (pinfunction "+_+") (pintype "passive"))
      (node (ref "C22") (pin "1") (pinfunction "1_1") (pintype "passive"))
      (node (ref "C23") (pin "1") (pinfunction "1_1") (pintype "passive"))
      (node (ref "C25") (pin "2") (pinfunction "2_2") (pintype "passive"))
      (node (ref "C28") (pin "1") (pinfunction "1_1") (pintype "passive"))
      (node (ref "C29") (pin "1") (pinfunction "1_1") (pintype "passive"))
      (node (ref "C5") (pin "1") (pinfunction "1_1") (pintype "passive"))
      (node (ref "C7") (pin "2") (pinfunction "2_2") (pintype "passive"))
      (node (ref "D1") (pin "C") (pinfunction "C_C") (pintype "passive"))
      (node (ref "U1") (pin "P$22") (pinfunction "VBB1_P$22") (pintype "bidirectional"))
      (node (ref "U1") (pin "P$28") (pinfunction "VBB2_P$28") (pintype "bidirectional"))
      (node (ref "U2") (pin "3") (pinfunction "IN_3") (pintype "input"))
      (node (ref "U3") (pin "P$22") (pinfunction "VBB1_P$22") (pintype "bidirectional"))
      (node (ref "U3") (pin "P$28") (pinfunction "VBB2_P$28") (pintype "bidirectional"))
      (node (ref "U4") (pin "P$22") (pinfunction "VBB1_P$22") (pintype "bidirectional"))
      (node (ref "U4") (pin "P$28") (pinfunction "VBB2_P$28") (pintype "bidirectional"))
      (node (ref "U5") (pin "P$22") (pinfunction "VBB1_P$22") (pintype "bidirectional"))
      (node (ref "U5") (pin "P$28") (pinfunction "VBB2_P$28") (pintype "bidirectional"))
    )
    (net (code "72") (name "VOUT") (class "Default")
      (node (ref "C1") (pin "1") (pinfunction "1_1") (pintype "passive"))
      (node (ref "C15") (pin "1") (pinfunction "1_1") (pintype "passive"))
      (node (ref "C21") (pin "1") (pinfunction "1_1") (pintype "passive"))
      (node (ref "C27") (pin "1") (pinfunction "1_1") (pintype "passive"))
      (node (ref "C3") (pin "A") (pinfunction "+_A") (pintype "passive"))
      (node (ref "C4") (pin "1") (pinfunction "1_1") (pintype "passive"))
      (node (ref "C9") (pin "1") (pinfunction "1_1") (pintype "passive"))
      (node (ref "JP16") (pin "13") (pinfunction "13_13") (pintype "passive"))
      (node (ref "JP16") (pin "14") (pinfunction "14_14") (pintype "passive"))
      (node (ref "LED5") (pin "A") (pinfunction "A_A") (pintype "passive"))
      (node (ref "R1") (pin "2") (pinfunction "2_2") (pintype "passive"))
      (node (ref "R10") (pin "3") (pinfunction "CW_3") (pintype "passive"))
      (node (ref "R15") (pin "1") (pinfunction "1_1") (pintype "passive"))
      (node (ref "R16") (pin "1") (pinfunction "1_1") (pintype "passive"))
      (node (ref "R17") (pin "3") (pinfunction "CW_3") (pintype "passive"))
      (node (ref "R22") (pin "1") (pinfunction "1_1") (pintype "passive"))
      (node (ref "R23") (pin "1") (pinfunction "1_1") (pintype "passive"))
      (node (ref "R24") (pin "3") (pinfunction "CW_3") (pintype "passive"))
      (node (ref "R29") (pin "1") (pinfunction "1_1") (pintype "passive"))
      (node (ref "R3") (pin "3") (pinfunction "CW_3") (pintype "passive"))
      (node (ref "R30") (pin "1") (pinfunction "1_1") (pintype "passive"))
      (node (ref "R31") (pin "1") (pinfunction "1_1") (pintype "passive"))
      (node (ref "R32") (pin "1") (pinfunction "1_1") (pintype "passive"))
      (node (ref "R33") (pin "1") (pinfunction "1_1") (pintype "passive"))
      (node (ref "R34") (pin "1") (pinfunction "1_1") (pintype "passive"))
      (node (ref "R37") (pin "1") (pinfunction "1_1") (pintype "passive"))
      (node (ref "R38") (pin "1") (pinfunction "1_1") (pintype "passive"))
      (node (ref "R39") (pin "1") (pinfunction "1_1") (pintype "passive"))
      (node (ref "R40") (pin "1") (pinfunction "1_1") (pintype "passive"))
      (node (ref "R41") (pin "1") (pinfunction "1_1") (pintype "passive"))
      (node (ref "R42") (pin "1") (pinfunction "1_1") (pintype "passive"))
      (node (ref "R43") (pin "1") (pinfunction "1_1") (pintype "passive"))
      (node (ref "R44") (pin "1") (pinfunction "1_1") (pintype "passive"))
      (node (ref "R45") (pin "1") (pinfunction "1_1") (pintype "passive"))
      (node (ref "R46") (pin "1") (pinfunction "1_1") (pintype "passive"))
      (node (ref "R47") (pin "1") (pinfunction "1_1") (pintype "passive"))
      (node (ref "R48") (pin "1") (pinfunction "1_1") (pintype "passive"))
      (node (ref "R8") (pin "1") (pinfunction "1_1") (pintype "passive"))
      (node (ref "R9") (pin "1") (pinfunction "1_1") (pintype "passive"))
      (node (ref "U1") (pin "P$15") (pinfunction "VDD_P$15") (pintype "power_in"))
      (node (ref "U2") (pin "4") (pinfunction "OUT_4") (pintype "output"))
      (node (ref "U3") (pin "P$15") (pinfunction "VDD_P$15") (pintype "power_in"))
      (node (ref "U4") (pin "P$15") (pinfunction "VDD_P$15") (pintype "power_in"))
      (node (ref "U5") (pin "P$15") (pinfunction "VDD_P$15") (pintype "power_in"))
    )
    (net (code "73") (name "unconnected-(JP16-Pad3)") (class "Default")
      (node (ref "JP16") (pin "3") (pinfunction "3_3") (pintype "passive"))
    )
    (net (code "74") (name "unconnected-(U1-NC-PadP$7)") (class "Default")
      (node (ref "U1") (pin "P$7") (pinfunction "NC_P$7") (pintype "no_connect"))
    )
    (net (code "75") (name "unconnected-(U1-NC-PadP$20)") (class "Default")
      (node (ref "U1") (pin "P$20") (pinfunction "NC_P$20") (pintype "no_connect"))
    )
    (net (code "76") (name "unconnected-(U1-NC-PadP$25)") (class "Default")
      (node (ref "U1") (pin "P$25") (pinfunction "NC_P$25") (pintype "no_connect"))
    )
    (net (code "77") (name "unconnected-(U3-NC-PadP$7)") (class "Default")
      (node (ref "U3") (pin "P$7") (pinfunction "NC_P$7") (pintype "no_connect"))
    )
    (net (code "78") (name "unconnected-(U3-NC-PadP$20)") (class "Default")
      (node (ref "U3") (pin "P$20") (pinfunction "NC_P$20") (pintype "no_connect"))
    )
    (net (code "79") (name "unconnected-(U3-NC-PadP$25)") (class "Default")
      (node (ref "U3") (pin "P$25") (pinfunction "NC_P$25") (pintype "no_connect"))
    )
    (net (code "80") (name "unconnected-(U4-NC-PadP$7)") (class "Default")
      (node (ref "U4") (pin "P$7") (pinfunction "NC_P$7") (pintype "no_connect"))
    )
    (net (code "81") (name "unconnected-(U4-NC-PadP$20)") (class "Default")
      (node (ref "U4") (pin "P$20") (pinfunction "NC_P$20") (pintype "no_connect"))
    )
    (net (code "82") (name "unconnected-(U4-NC-PadP$25)") (class "Default")
      (node (ref "U4") (pin "P$25") (pinfunction "NC_P$25") (pintype "no_connect"))
    )
    (net (code "83") (name "unconnected-(U5-NC-PadP$7)") (class "Default")
      (node (ref "U5") (pin "P$7") (pinfunction "NC_P$7") (pintype "no_connect"))
    )
    (net (code "84") (name "unconnected-(U5-NC-PadP$20)") (class "Default")
      (node (ref "U5") (pin "P$20") (pinfunction "NC_P$20") (pintype "no_connect"))
    )
    (net (code "85") (name "unconnected-(U5-NC-PadP$25)") (class "Default")
      (node (ref "U5") (pin "P$25") (pinfunction "NC_P$25") (pintype "no_connect"))
    )
  )
)
